# INT_mPCIeX2_SIM.net
KiCad netlist of a schematic drawn in Altium Designer
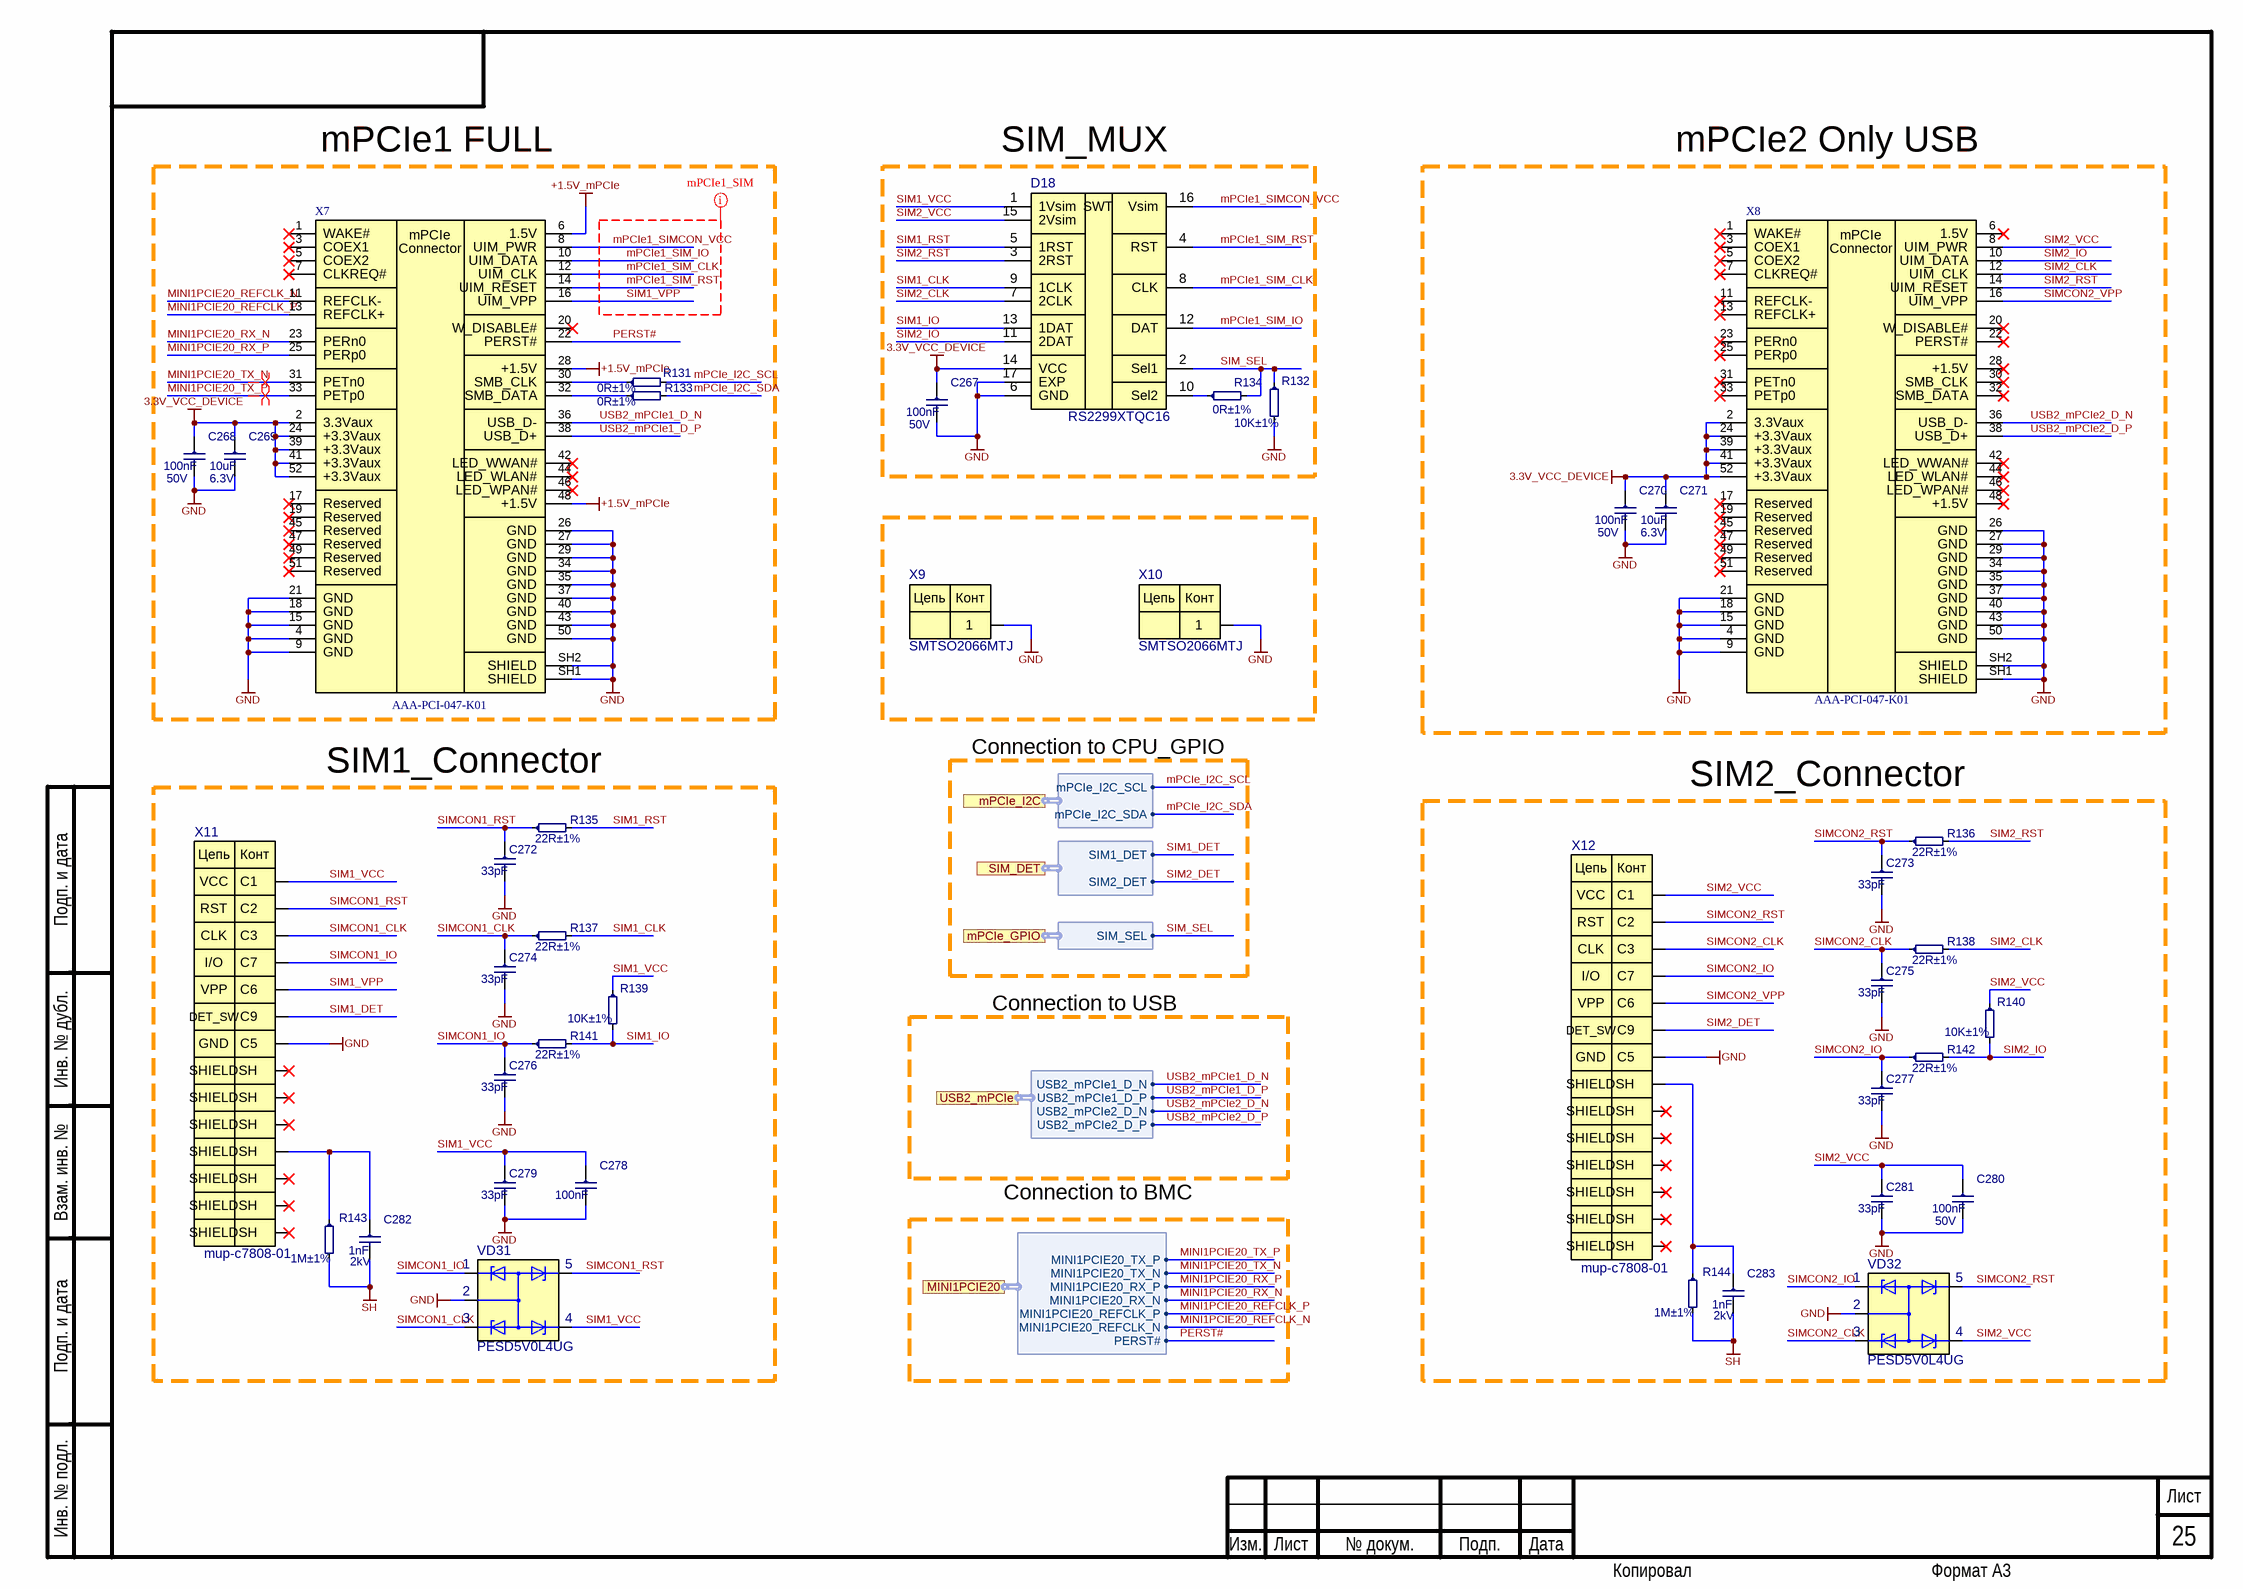
[diagram p0: INT_mPCIeX2_SIM.SchDoc]

(export (version "E")
  (design (tool "Eeschema 10.0.6"))
  (components
    (comp (ref "C267")
      (value "100nF")
      (footprint "C0402")
      (description "Ceramic Capacitor 0402 100nF ±10% 50V X7R")
      (fields
        (field (name "VOLTAGE") "50V")
        (field (name "PART NUMBER") "0402-X7R-50V-0.1uF±10%")
        (field (name "TOLERANCE") "10%")
      )
      (libsource (lib "ATB") (part "C"))
    )
    (comp (ref "C268")
      (value "100nF")
      (footprint "C0402")
      (description "Ceramic Capacitor 0402 100nF ±10% 50V X7R")
      (fields
        (field (name "VOLTAGE") "50V")
        (field (name "PART NUMBER") "0402-X7R-50V-0.1uF±10%")
        (field (name "TOLERANCE") "10%")
      )
      (libsource (lib "ATB") (part "C"))
    )
    (comp (ref "C269")
      (value "10uF")
      (footprint "C0402")
      (fields
        (field (name "VOLTAGE") "6.3V")
        (field (name "PART NUMBER") "0402-X5R-6.3V-10uF±20%")
        (field (name "TOLERANCE") "20%")
        (field (name "MANUFACTURER") "Yageo")
      )
      (libsource (lib "ATB") (part "C"))
    )
    (comp (ref "C270")
      (value "100nF")
      (footprint "C0402")
      (description "Ceramic Capacitor 0402 100nF ±10% 50V X7R")
      (fields
        (field (name "VOLTAGE") "50V")
        (field (name "PART NUMBER") "0402-X7R-50V-0.1uF±10%")
        (field (name "TOLERANCE") "10%")
      )
      (libsource (lib "ATB") (part "C"))
    )
    (comp (ref "C271")
      (value "10uF")
      (footprint "C0402")
      (fields
        (field (name "VOLTAGE") "6.3V")
        (field (name "PART NUMBER") "0402-X5R-6.3V-10uF±20%")
        (field (name "TOLERANCE") "20%")
        (field (name "MANUFACTURER") "Yageo")
      )
      (libsource (lib "ATB") (part "C"))
    )
    (comp (ref "C272")
      (value "33pF")
      (footprint "C0402")
      (fields
        (field (name "VOLTAGE") "50V")
        (field (name "PART NUMBER") "0402-NP0-50V-33pF±5%")
        (field (name "TOLERANCE") "5%")
      )
      (libsource (lib "ATB") (part "C"))
    )
    (comp (ref "C273")
      (value "33pF")
      (footprint "C0402")
      (fields
        (field (name "VOLTAGE") "50V")
        (field (name "PART NUMBER") "0402-NP0-50V-33pF±5%")
        (field (name "TOLERANCE") "5%")
      )
      (libsource (lib "ATB") (part "C"))
    )
    (comp (ref "C274")
      (value "33pF")
      (footprint "C0402")
      (fields
        (field (name "VOLTAGE") "50V")
        (field (name "PART NUMBER") "0402-NP0-50V-33pF±5%")
        (field (name "TOLERANCE") "5%")
      )
      (libsource (lib "ATB") (part "C"))
    )
    (comp (ref "C275")
      (value "33pF")
      (footprint "C0402")
      (fields
        (field (name "VOLTAGE") "50V")
        (field (name "PART NUMBER") "0402-NP0-50V-33pF±5%")
        (field (name "TOLERANCE") "5%")
      )
      (libsource (lib "ATB") (part "C"))
    )
    (comp (ref "C276")
      (value "33pF")
      (footprint "C0402")
      (fields
        (field (name "VOLTAGE") "50V")
        (field (name "PART NUMBER") "0402-NP0-50V-33pF±5%")
        (field (name "TOLERANCE") "5%")
      )
      (libsource (lib "ATB") (part "C"))
    )
    (comp (ref "C277")
      (value "33pF")
      (footprint "C0402")
      (fields
        (field (name "VOLTAGE") "50V")
        (field (name "PART NUMBER") "0402-NP0-50V-33pF±5%")
        (field (name "TOLERANCE") "5%")
      )
      (libsource (lib "ATB") (part "C"))
    )
    (comp (ref "C278")
      (value "100nF")
      (footprint "C0402")
      (description "Ceramic Capacitor 0402 100nF ±10% 50V X7R")
      (fields (field (name "VOLTAGE") "50V") (field (name "PART NUMBER") "0402-X7R-50V-0.1uF±10%"))
      (libsource (lib "ATB") (part "C"))
    )
    (comp (ref "C279")
      (value "33pF")
      (footprint "C0402")
      (fields
        (field (name "VOLTAGE") "50V")
        (field (name "PART NUMBER") "0402-NP0-50V-33pF±5%")
        (field (name "TOLERANCE") "5%")
      )
      (libsource (lib "ATB") (part "C"))
    )
    (comp (ref "C280")
      (value "100nF")
      (footprint "C0402")
      (description "Ceramic Capacitor 0402 100nF ±10% 50V X7R")
      (fields
        (field (name "VOLTAGE") "50V")
        (field (name "PART NUMBER") "0402-X7R-50V-0.1uF±10%")
        (field (name "TOLERANCE") "10%")
      )
      (libsource (lib "ATB") (part "C"))
    )
    (comp (ref "C281")
      (value "33pF")
      (footprint "C0402")
      (fields
        (field (name "VOLTAGE") "50V")
        (field (name "PART NUMBER") "0402-NP0-50V-33pF±5%")
        (field (name "TOLERANCE") "5%")
      )
      (libsource (lib "ATB") (part "C"))
    )
    (comp (ref "C282")
      (value "1nF")
      (footprint "C1812")
      (fields
        (field (name "VOLTAGE") "2kV")
        (field (name "PART NUMBER") "1812-C0G-2kV-1nF±10%")
        (field (name "TOLERANCE") "5%")
        (field (name "MANUFACTURER") "FH")
      )
      (libsource (lib "ATB") (part "C"))
    )
    (comp (ref "C283")
      (value "1nF")
      (footprint "C1812")
      (fields
        (field (name "VOLTAGE") "2kV")
        (field (name "PART NUMBER") "1812-C0G-2kV-1nF±10%")
        (field (name "TOLERANCE") "5%")
        (field (name "MANUFACTURER") "FH")
      )
      (libsource (lib "ATB") (part "C"))
    )
    (comp (ref "D18")
      (value "RS2299XTQC16")
      (footprint "RS2299XTQC16")
      (description "Analog Switches")
      (fields (field (name "MANUFACTURER") "RUNIC Tech"))
      (libsource (lib "LIB_RK") (part "RS2299XTQC16"))
    )
    (comp (ref "R131")
      (value "0R±1%")
      (footprint "R0402")
      (description "Chip Resistor 0402 0Ω ±1% 50V ±100ppm/℃ Thick Film")
      (fields (field (name "PART NUMBER") "0402-0.0625W-0R-100ppm±1%") (field (name "TOLERANCE") "1%"))
      (libsource (lib "ATB") (part "R"))
    )
    (comp (ref "R132")
      (value "10K±1%")
      (footprint "R0402")
      (description "Chip Resistor 0402 10kΩ ±1% 50V ±100ppm/℃ Thick Film")
      (fields (field (name "PART NUMBER") "0402-0.0625W-10K-100ppm±1%") (field (name "TOLERANCE") "1%"))
      (libsource (lib "ATB") (part "R"))
    )
    (comp (ref "R133")
      (value "0R±1%")
      (footprint "R0402")
      (description "Chip Resistor 0402 0Ω ±1% 50V ±100ppm/℃ Thick Film")
      (fields (field (name "PART NUMBER") "0402-0.0625W-0R-100ppm±1%") (field (name "TOLERANCE") "1%"))
      (libsource (lib "ATB") (part "R"))
    )
    (comp (ref "R134")
      (value "0R±1%")
      (footprint "R0402")
      (description "Chip Resistor 0402 0Ω ±1% 50V ±100ppm/℃ Thick Film")
      (fields (field (name "PART NUMBER") "0402-0.0625W-0R-100ppm±1%") (field (name "TOLERANCE") "1%"))
      (libsource (lib "ATB") (part "R"))
    )
    (comp (ref "R135")
      (value "22R±1%")
      (footprint "R0402")
      (description "Chip Resistor 0402 22Ω ±1% 50V ±100ppm/℃ Thick Film")
      (fields (field (name "PART NUMBER") "0402-0.0625W-22R-100ppm±1%") (field (name "TOLERANCE") "1%"))
      (libsource (lib "ATB") (part "R"))
    )
    (comp (ref "R136")
      (value "22R±1%")
      (footprint "R0402")
      (description "Chip Resistor 0402 22Ω ±1% 50V ±100ppm/℃ Thick Film")
      (fields (field (name "PART NUMBER") "0402-0.0625W-22R-100ppm±1%") (field (name "TOLERANCE") "1%"))
      (libsource (lib "ATB") (part "R"))
    )
    (comp (ref "R137")
      (value "22R±1%")
      (footprint "R0402")
      (description "Chip Resistor 0402 22Ω ±1% 50V ±100ppm/℃ Thick Film")
      (fields (field (name "PART NUMBER") "0402-0.0625W-22R-100ppm±1%") (field (name "TOLERANCE") "1%"))
      (libsource (lib "ATB") (part "R"))
    )
    (comp (ref "R138")
      (value "22R±1%")
      (footprint "R0402")
      (description "Chip Resistor 0402 22Ω ±1% 50V ±100ppm/℃ Thick Film")
      (fields (field (name "PART NUMBER") "0402-0.0625W-22R-100ppm±1%") (field (name "TOLERANCE") "1%"))
      (libsource (lib "ATB") (part "R"))
    )
    (comp (ref "R139")
      (value "10K±1%")
      (footprint "R0402")
      (description "Chip Resistor 0402 10kΩ ±1% 50V ±100ppm/℃ Thick Film")
      (fields (field (name "PART NUMBER") "0402-0.0625W-10K-100ppm±1%") (field (name "TOLERANCE") "1%"))
      (libsource (lib "ATB") (part "R"))
    )
    (comp (ref "R140")
      (value "10K±1%")
      (footprint "R0402")
      (description "Chip Resistor 0402 10kΩ ±1% 50V ±100ppm/℃ Thick Film")
      (fields (field (name "PART NUMBER") "0402-0.0625W-10K-100ppm±1%") (field (name "TOLERANCE") "1%"))
      (libsource (lib "ATB") (part "R"))
    )
    (comp (ref "R141")
      (value "22R±1%")
      (footprint "R0402")
      (description "Chip Resistor 0402 22Ω ±1% 50V ±100ppm/℃ Thick Film")
      (fields (field (name "PART NUMBER") "0402-0.0625W-22R-100ppm±1%") (field (name "TOLERANCE") "1%"))
      (libsource (lib "ATB") (part "R"))
    )
    (comp (ref "R142")
      (value "22R±1%")
      (footprint "R0402")
      (description "Chip Resistor 0402 22Ω ±1% 50V ±100ppm/℃ Thick Film")
      (fields (field (name "PART NUMBER") "0402-0.0625W-22R-100ppm±1%") (field (name "TOLERANCE") "1%"))
      (libsource (lib "ATB") (part "R"))
    )
    (comp (ref "R143")
      (value "1M±1%")
      (footprint "R1206")
      (description "Chip Resistor 1206 1MΩ ±1% 200V ±100ppm/℃ Thick Film")
      (fields (field (name "PART NUMBER") "1206-0.25W-1M-100ppm±1%") (field (name "TOLERANCE") "1%"))
      (libsource (lib "ATB") (part "R"))
    )
    (comp (ref "R144")
      (value "1M±1%")
      (footprint "R1206")
      (description "Chip Resistor 1206 1MΩ ±1% 200V ±100ppm/℃ Thick Film")
      (fields (field (name "PART NUMBER") "1206-0.25W-1M-100ppm±1%") (field (name "TOLERANCE") "1%"))
      (libsource (lib "ATB") (part "R"))
    )
    (comp (ref "VD31")
      (value "PESD5V0L4UG")
      (footprint "TSSOP5-5")
      (description "Low capacitance unidirectional quadruple ESD protectiondiode arrays")
      (fields (field (name "MANUFACTURER") "Tech Public Co."))
      (libsource (lib "ATB") (part "PESDxL4UG/W"))
    )
    (comp (ref "VD32")
      (value "PESD5V0L4UG")
      (footprint "TSSOP5-5")
      (description "Low capacitance unidirectional quadruple ESD protectiondiode arrays")
      (fields (field (name "MANUFACTURER") "Tech Public Co."))
      (libsource (lib "ATB") (part "PESDxL4UG/W"))
    )
    (comp (ref "X7")
      (value "AAA-PCI-047-K01")
      (footprint "AAA-PCI-047-K01")
      (description "mPCI-E Surface Mount 52 SMD,P=0.8mm Card Edge Connectors")
      (fields (field (name "MANUFACTURER") "LOTES"))
      (libsource (lib "LIB_RK") (part "AAA-PCI-047-K01"))
    )
    (comp (ref "X8")
      (value "AAA-PCI-047-K01")
      (footprint "AAA-PCI-047-K01")
      (description "mPCI-E Surface Mount 52 SMD,P=0.8mm Card Edge Connectors")
      (fields (field (name "MANUFACTURER") "LOTES"))
      (libsource (lib "LIB_RK") (part "AAA-PCI-047-K01"))
    )
    (comp (ref "X9")
      (value "SMTSO2066MTJ")
      (footprint "SMTSO2066MTJ")
      (fields (field (name "MANUFACTURER") "Sinhoo"))
      (libsource (lib "LIB_RK") (part "SMTSO2066MTJ"))
    )
    (comp (ref "X10")
      (value "SMTSO2066MTJ")
      (footprint "SMTSO2066MTJ")
      (fields (field (name "MANUFACTURER") "Sinhoo"))
      (libsource (lib "LIB_RK") (part "SMTSO2066MTJ"))
    )
    (comp (ref "X11")
      (value "mup-c7808-01")
      (footprint "mup-c7808")
      (fields (field (name "MANUFACTURER") "MUP"))
      (libsource (lib "LIB_RK") (part "mup-c7808"))
    )
    (comp (ref "X12")
      (value "mup-c7808-01")
      (footprint "mup-c7808")
      (fields (field (name "MANUFACTURER") "MUP"))
      (libsource (lib "LIB_RK") (part "mup-c7808"))
    )
  )
  (nets
    (net (code "6") (name "+1.5V_mPCIe") (class "Default")
      (node (ref "X7") (pin "28") (pinfunction "+1.5V_28") (pintype "passive"))
      (node (ref "X7") (pin "48") (pinfunction "+1.5V_48") (pintype "passive"))
      (node (ref "X7") (pin "6") (pinfunction "1.5V_6") (pintype "passive"))
    )
    (net (code "7") (name "/MINI1PCIE20_REFCLK_N") (class "Default")
      (node (ref "X7") (pin "11") (pinfunction "REFCLK-_11") (pintype "passive"))
    )
    (net (code "8") (name "/MINI1PCIE20_REFCLK_P") (class "Default")
      (node (ref "X7") (pin "13") (pinfunction "REFCLK+_13") (pintype "passive"))
    )
    (net (code "9") (name "/MINI1PCIE20_RX_N") (class "Default")
      (node (ref "X7") (pin "23") (pinfunction "PERn0_23") (pintype "passive"))
    )
    (net (code "10") (name "/MINI1PCIE20_RX_P") (class "Default")
      (node (ref "X7") (pin "25") (pinfunction "PERp0_25") (pintype "passive"))
    )
    (net (code "11") (name "/MINI1PCIE20_TX_N") (class "Default")
      (node (ref "X7") (pin "31") (pinfunction "PETn0_31") (pintype "passive"))
    )
    (net (code "12") (name "/MINI1PCIE20_TX_P") (class "Default")
      (node (ref "X7") (pin "33") (pinfunction "РЕТр0_33") (pintype "passive"))
    )
    (net (code "13") (name "/PERST#") (class "Default")
      (node (ref "X7") (pin "22") (pinfunction "PERST#_22") (pintype "passive"))
    )
    (net (code "14") (name "/SIM1_CLK") (class "Default")
      (node (ref "D18") (pin "9") (pinfunction "1CLK_9") (pintype "passive"))
      (node (ref "R137") (pin "2") (pinfunction "2_2") (pintype "passive"))
    )
    (net (code "15") (name "/SIM1_DET") (class "Default")
      (node (ref "X11") (pin "C9") (pinfunction "C9_C9") (pintype "passive"))
    )
    (net (code "16") (name "/SIM1_IO") (class "Default")
      (node (ref "D18") (pin "13") (pinfunction "1DAT_13") (pintype "passive"))
      (node (ref "R139") (pin "2") (pinfunction "2_2") (pintype "passive"))
      (node (ref "R141") (pin "2") (pinfunction "2_2") (pintype "passive"))
    )
    (net (code "17") (name "/SIM1_RST") (class "Default")
      (node (ref "D18") (pin "5") (pinfunction "1RST_5") (pintype "passive"))
      (node (ref "R135") (pin "2") (pinfunction "2_2") (pintype "passive"))
    )
    (net (code "18") (name "/SIM1_VCC") (class "Default")
      (node (ref "C278") (pin "1") (pinfunction "1_1") (pintype "passive"))
      (node (ref "C279") (pin "1") (pinfunction "1_1") (pintype "passive"))
      (node (ref "D18") (pin "1") (pinfunction "1Vsim_1") (pintype "passive"))
      (node (ref "R139") (pin "1") (pinfunction "1_1") (pintype "passive"))
      (node (ref "VD31") (pin "4") (pinfunction "4_4") (pintype "passive"))
      (node (ref "X11") (pin "C1") (pinfunction "C1_C1") (pintype "passive"))
    )
    (net (code "19") (name "/SIM1_VPP") (class "Default")
      (node (ref "X11") (pin "C6") (pinfunction "C6_C6") (pintype "passive"))
      (node (ref "X7") (pin "16") (pinfunction "UIM_VPP_16") (pintype "passive"))
    )
    (net (code "20") (name "/SIM2_CLK") (class "Default")
      (node (ref "D18") (pin "7") (pinfunction "2CLK_7") (pintype "passive"))
      (node (ref "R138") (pin "2") (pinfunction "2_2") (pintype "passive"))
      (node (ref "X8") (pin "12") (pinfunction "UIM_CLK_12") (pintype "passive"))
    )
    (net (code "21") (name "/SIM2_DET") (class "Default")
      (node (ref "X12") (pin "C9") (pinfunction "C9_C9") (pintype "passive"))
    )
    (net (code "22") (name "/SIM2_IO") (class "Default")
      (node (ref "D18") (pin "11") (pinfunction "2DAT_11") (pintype "passive"))
      (node (ref "R140") (pin "2") (pinfunction "2_2") (pintype "passive"))
      (node (ref "R142") (pin "2") (pinfunction "2_2") (pintype "passive"))
      (node (ref "X8") (pin "10") (pinfunction "UIM_DATA_10") (pintype "passive"))
    )
    (net (code "23") (name "/SIM2_RST") (class "Default")
      (node (ref "D18") (pin "3") (pinfunction "2RST_3") (pintype "passive"))
      (node (ref "R136") (pin "2") (pinfunction "2_2") (pintype "passive"))
      (node (ref "X8") (pin "14") (pinfunction "UIM_RESET_14") (pintype "passive"))
    )
    (net (code "24") (name "/SIM2_VCC") (class "Default")
      (node (ref "C280") (pin "1") (pinfunction "1_1") (pintype "passive"))
      (node (ref "C281") (pin "1") (pinfunction "1_1") (pintype "passive"))
      (node (ref "D18") (pin "15") (pinfunction "2Vsim_15") (pintype "passive"))
      (node (ref "R140") (pin "1") (pinfunction "1_1") (pintype "passive"))
      (node (ref "VD32") (pin "4") (pinfunction "4_4") (pintype "passive"))
      (node (ref "X12") (pin "C1") (pinfunction "C1_C1") (pintype "passive"))
      (node (ref "X8") (pin "8") (pinfunction "UIM_PWR_8") (pintype "passive"))
    )
    (net (code "25") (name "/SIMCON1_CLK") (class "Default")
      (node (ref "C274") (pin "1") (pinfunction "1_1") (pintype "passive"))
      (node (ref "R137") (pin "1") (pinfunction "1_1") (pintype "passive"))
      (node (ref "VD31") (pin "3") (pinfunction "3_3") (pintype "passive"))
      (node (ref "X11") (pin "C3") (pinfunction "C3_C3") (pintype "passive"))
    )
    (net (code "26") (name "/SIMCON1_IO") (class "Default")
      (node (ref "C276") (pin "1") (pinfunction "1_1") (pintype "passive"))
      (node (ref "R141") (pin "1") (pinfunction "1_1") (pintype "passive"))
      (node (ref "VD31") (pin "1") (pinfunction "1_1") (pintype "passive"))
      (node (ref "X11") (pin "C7") (pinfunction "C7_C7") (pintype "passive"))
    )
    (net (code "27") (name "/SIMCON1_RST") (class "Default")
      (node (ref "C272") (pin "1") (pinfunction "1_1") (pintype "passive"))
      (node (ref "R135") (pin "1") (pinfunction "1_1") (pintype "passive"))
      (node (ref "VD31") (pin "5") (pinfunction "5_5") (pintype "passive"))
      (node (ref "X11") (pin "C2") (pinfunction "C2_C2") (pintype "passive"))
    )
    (net (code "28") (name "/SIMCON2_CLK") (class "Default")
      (node (ref "C275") (pin "1") (pinfunction "1_1") (pintype "passive"))
      (node (ref "R138") (pin "1") (pinfunction "1_1") (pintype "passive"))
      (node (ref "VD32") (pin "3") (pinfunction "3_3") (pintype "passive"))
      (node (ref "X12") (pin "C3") (pinfunction "C3_C3") (pintype "passive"))
    )
    (net (code "29") (name "/SIMCON2_IO") (class "Default")
      (node (ref "C277") (pin "1") (pinfunction "1_1") (pintype "passive"))
      (node (ref "R142") (pin "1") (pinfunction "1_1") (pintype "passive"))
      (node (ref "VD32") (pin "1") (pinfunction "1_1") (pintype "passive"))
      (node (ref "X12") (pin "C7") (pinfunction "C7_C7") (pintype "passive"))
    )
    (net (code "30") (name "/SIMCON2_RST") (class "Default")
      (node (ref "C273") (pin "1") (pinfunction "1_1") (pintype "passive"))
      (node (ref "R136") (pin "1") (pinfunction "1_1") (pintype "passive"))
      (node (ref "VD32") (pin "5") (pinfunction "5_5") (pintype "passive"))
      (node (ref "X12") (pin "C2") (pinfunction "C2_C2") (pintype "passive"))
    )
    (net (code "31") (name "/SIMCON2_VPP") (class "Default")
      (node (ref "X12") (pin "C6") (pinfunction "C6_C6") (pintype "passive"))
      (node (ref "X8") (pin "16") (pinfunction "UIM_VPP_16") (pintype "passive"))
    )
    (net (code "32") (name "/SIM_SEL") (class "Default")
      (node (ref "D18") (pin "2") (pinfunction "Sel1_2") (pintype "passive"))
      (node (ref "R132") (pin "1") (pinfunction "1_1") (pintype "passive"))
      (node (ref "R134") (pin "2") (pinfunction "2_2") (pintype "passive"))
    )
    (net (code "33") (name "/USB2_mPCIe1_D_N") (class "Default")
      (node (ref "X7") (pin "36") (pinfunction "USB_D-_36") (pintype "passive"))
    )
    (net (code "34") (name "/USB2_mPCIe1_D_P") (class "Default")
      (node (ref "X7") (pin "38") (pinfunction "USB_D+_38") (pintype "passive"))
    )
    (net (code "35") (name "/USB2_mPCIe2_D_N") (class "Default")
      (node (ref "X8") (pin "36") (pinfunction "USB_D-_36") (pintype "passive"))
    )
    (net (code "36") (name "/USB2_mPCIe2_D_P") (class "Default")
      (node (ref "X8") (pin "38") (pinfunction "USB_D+_38") (pintype "passive"))
    )
    (net (code "37") (name "/mPCIe1_SIMCON_VCC") (class "Default")
      (node (ref "D18") (pin "16") (pinfunction "Vsim_16") (pintype "passive"))
      (node (ref "X7") (pin "8") (pinfunction "UIM_PWR_8") (pintype "passive"))
    )
    (net (code "38") (name "/mPCIe1_SIM_CLK") (class "Default")
      (node (ref "D18") (pin "8") (pinfunction "CLK_8") (pintype "passive"))
      (node (ref "X7") (pin "12") (pinfunction "UIM_CLK_12") (pintype "passive"))
    )
    (net (code "39") (name "/mPCIe1_SIM_IO") (class "Default")
      (node (ref "D18") (pin "12") (pinfunction "DAT_12") (pintype "passive"))
      (node (ref "X7") (pin "10") (pinfunction "UIM_DATA_10") (pintype "passive"))
    )
    (net (code "40") (name "/mPCIe1_SIM_RST") (class "Default")
      (node (ref "D18") (pin "4") (pinfunction "RST_4") (pintype "passive"))
      (node (ref "X7") (pin "14") (pinfunction "UIM_RESET_14") (pintype "passive"))
    )
    (net (code "41") (name "/mPCIe_I2C_SCL") (class "Default")
      (node (ref "R131") (pin "2") (pinfunction "2_2") (pintype "passive"))
    )
    (net (code "42") (name "/mPCIe_I2C_SDA") (class "Default")
      (node (ref "R133") (pin "2") (pinfunction "2_2") (pintype "passive"))
    )
    (net (code "48") (name "3.3V_VCC_DEVICE") (class "Default")
      (node (ref "C267") (pin "1") (pinfunction "1_1") (pintype "passive"))
      (node (ref "C268") (pin "1") (pinfunction "1_1") (pintype "passive"))
      (node (ref "C269") (pin "1") (pinfunction "1_1") (pintype "passive"))
      (node (ref "C270") (pin "1") (pinfunction "1_1") (pintype "passive"))
      (node (ref "C271") (pin "1") (pinfunction "1_1") (pintype "passive"))
      (node (ref "D18") (pin "14") (pinfunction "VCC_14") (pintype "passive"))
      (node (ref "X7") (pin "2") (pinfunction "3.3Vaux_2") (pintype "passive"))
      (node (ref "X7") (pin "24") (pinfunction "+3.3Vaux_24") (pintype "passive"))
      (node (ref "X7") (pin "39") (pinfunction "+3.3Vaux_39") (pintype "passive"))
      (node (ref "X7") (pin "41") (pinfunction "+3.3Vaux_41") (pintype "passive"))
      (node (ref "X7") (pin "52") (pinfunction "+3.3Vaux_52") (pintype "passive"))
      (node (ref "X8") (pin "2") (pinfunction "3.3Vaux_2") (pintype "passive"))
      (node (ref "X8") (pin "24") (pinfunction "+3.3Vaux_24") (pintype "passive"))
      (node (ref "X8") (pin "39") (pinfunction "+3.3Vaux_39") (pintype "passive"))
      (node (ref "X8") (pin "41") (pinfunction "+3.3Vaux_41") (pintype "passive"))
      (node (ref "X8") (pin "52") (pinfunction "+3.3Vaux_52") (pintype "passive"))
    )
    (net (code "49") (name "GND") (class "Default")
      (node (ref "C267") (pin "2") (pinfunction "2_2") (pintype "passive"))
      (node (ref "C268") (pin "2") (pinfunction "2_2") (pintype "passive"))
      (node (ref "C269") (pin "2") (pinfunction "2_2") (pintype "passive"))
      (node (ref "C270") (pin "2") (pinfunction "2_2") (pintype "passive"))
      (node (ref "C271") (pin "2") (pinfunction "2_2") (pintype "passive"))
      (node (ref "C272") (pin "2") (pinfunction "2_2") (pintype "passive"))
      (node (ref "C273") (pin "2") (pinfunction "2_2") (pintype "passive"))
      (node (ref "C274") (pin "2") (pinfunction "2_2") (pintype "passive"))
      (node (ref "C275") (pin "2") (pinfunction "2_2") (pintype "passive"))
      (node (ref "C276") (pin "2") (pinfunction "2_2") (pintype "passive"))
      (node (ref "C277") (pin "2") (pinfunction "2_2") (pintype "passive"))
      (node (ref "C278") (pin "2") (pinfunction "2_2") (pintype "passive"))
      (node (ref "C279") (pin "2") (pinfunction "2_2") (pintype "passive"))
      (node (ref "C280") (pin "2") (pinfunction "2_2") (pintype "passive"))
      (node (ref "C281") (pin "2") (pinfunction "2_2") (pintype "passive"))
      (node (ref "D18") (pin "17") (pinfunction "EXP_17") (pintype "passive"))
      (node (ref "D18") (pin "6") (pinfunction "GND_6") (pintype "passive"))
      (node (ref "R132") (pin "2") (pinfunction "2_2") (pintype "passive"))
      (node (ref "VD31") (pin "2") (pinfunction "2_2") (pintype "passive"))
      (node (ref "VD32") (pin "2") (pinfunction "2_2") (pintype "passive"))
      (node (ref "X10") (pin "1") (pinfunction "1_1") (pintype "passive"))
      (node (ref "X11") (pin "C5") (pinfunction "C5_C5") (pintype "passive"))
      (node (ref "X12") (pin "C5") (pinfunction "C5_C5") (pintype "passive"))
      (node (ref "X7") (pin "15") (pinfunction "GND_15") (pintype "passive"))
      (node (ref "X7") (pin "18") (pinfunction "GND_18") (pintype "passive"))
      (node (ref "X7") (pin "21") (pinfunction "GND_21") (pintype "passive"))
      (node (ref "X7") (pin "26") (pinfunction "GND_26") (pintype "passive"))
      (node (ref "X7") (pin "27") (pinfunction "GND_27") (pintype "passive"))
      (node (ref "X7") (pin "29") (pinfunction "GND_29") (pintype "passive"))
      (node (ref "X7") (pin "34") (pinfunction "GND_34") (pintype "passive"))
      (node (ref "X7") (pin "35") (pinfunction "GND_35") (pintype "passive"))
      (node (ref "X7") (pin "37") (pinfunction "GND_37") (pintype "passive"))
      (node (ref "X7") (pin "4") (pinfunction "GND_4") (pintype "passive"))
      (node (ref "X7") (pin "40") (pinfunction "GND_40") (pintype "passive"))
      (node (ref "X7") (pin "43") (pinfunction "GND_43") (pintype "passive"))
      (node (ref "X7") (pin "50") (pinfunction "GND_50") (pintype "passive"))
      (node (ref "X7") (pin "9") (pinfunction "GND_9") (pintype "passive"))
      (node (ref "X7") (pin "SH1") (pinfunction "SHIELD_SH1") (pintype "passive"))
      (node (ref "X7") (pin "SH2") (pinfunction "SHIELD_SH2") (pintype "passive"))
      (node (ref "X8") (pin "15") (pinfunction "GND_15") (pintype "passive"))
      (node (ref "X8") (pin "18") (pinfunction "GND_18") (pintype "passive"))
      (node (ref "X8") (pin "21") (pinfunction "GND_21") (pintype "passive"))
      (node (ref "X8") (pin "26") (pinfunction "GND_26") (pintype "passive"))
      (node (ref "X8") (pin "27") (pinfunction "GND_27") (pintype "passive"))
      (node (ref "X8") (pin "29") (pinfunction "GND_29") (pintype "passive"))
      (node (ref "X8") (pin "34") (pinfunction "GND_34") (pintype "passive"))
      (node (ref "X8") (pin "35") (pinfunction "GND_35") (pintype "passive"))
      (node (ref "X8") (pin "37") (pinfunction "GND_37") (pintype "passive"))
      (node (ref "X8") (pin "4") (pinfunction "GND_4") (pintype "passive"))
      (node (ref "X8") (pin "40") (pinfunction "GND_40") (pintype "passive"))
      (node (ref "X8") (pin "43") (pinfunction "GND_43") (pintype "passive"))
      (node (ref "X8") (pin "50") (pinfunction "GND_50") (pintype "passive"))
      (node (ref "X8") (pin "9") (pinfunction "GND_9") (pintype "passive"))
      (node (ref "X8") (pin "SH1") (pinfunction "SHIELD_SH1") (pintype "passive"))
      (node (ref "X8") (pin "SH2") (pinfunction "SHIELD_SH2") (pintype "passive"))
      (node (ref "X9") (pin "1") (pinfunction "1_1") (pintype "passive"))
    )
    (net (code "50") (name "Net-(C282-Pad1)") (class "Default")
      (node (ref "C282") (pin "1") (pinfunction "1_1") (pintype "passive"))
      (node (ref "R143") (pin "1") (pinfunction "1_1") (pintype "passive"))
      (node (ref "X11") (pin "SH4") (pinfunction "SH_SH4") (pintype "passive"))
    )
    (net (code "51") (name "Net-(C283-Pad1)") (class "Default")
      (node (ref "C283") (pin "1") (pinfunction "1_1") (pintype "passive"))
      (node (ref "R144") (pin "1") (pinfunction "1_1") (pintype "passive"))
      (node (ref "X12") (pin "SH1") (pinfunction "SH_SH1") (pintype "passive"))
    )
    (net (code "52") (name "Net-(D18-Sel2)") (class "Default")
      (node (ref "D18") (pin "10") (pinfunction "Sel2_10") (pintype "passive"))
      (node (ref "R134") (pin "1") (pinfunction "1_1") (pintype "passive"))
    )
    (net (code "53") (name "Net-(X7-SMB_CLK)") (class "Default")
      (node (ref "R131") (pin "1") (pinfunction "1_1") (pintype "passive"))
      (node (ref "X7") (pin "30") (pinfunction "SMB_CLK_30") (pintype "passive"))
    )
    (net (code "54") (name "Net-(X7-SMB_DATA)") (class "Default")
      (node (ref "R133") (pin "1") (pinfunction "1_1") (pintype "passive"))
      (node (ref "X7") (pin "32") (pinfunction "SMB_DATA_32") (pintype "passive"))
    )
    (net (code "55") (name "SH") (class "Default")
      (node (ref "C282") (pin "2") (pinfunction "2_2") (pintype "passive"))
      (node (ref "C283") (pin "2") (pinfunction "2_2") (pintype "passive"))
      (node (ref "R143") (pin "2") (pinfunction "2_2") (pintype "passive"))
      (node (ref "R144") (pin "2") (pinfunction "2_2") (pintype "passive"))
    )
    (net (code "56") (name "unconnected-(X7-CLKREQ#-Pad7)") (class "Default")
      (node (ref "X7") (pin "7") (pinfunction "CLKREQ#_7") (pintype "passive+no_connect"))
    )
    (net (code "57") (name "unconnected-(X7-LED_WLAN#-Pad44)") (class "Default")
      (node (ref "X7") (pin "44") (pinfunction "LED_WLAN#_44") (pintype "passive+no_connect"))
    )
    (net (code "58") (name "unconnected-(X7-LED_WPAN#-Pad46)") (class "Default")
      (node (ref "X7") (pin "46") (pinfunction "LED_WPAN#_46") (pintype "passive+no_connect"))
    )
    (net (code "59") (name "unconnected-(X7-LED_WWAN#-Pad42)") (class "Default")
      (node (ref "X7") (pin "42") (pinfunction "LED_WWAN#_42") (pintype "passive+no_connect"))
    )
    (net (code "60") (name "unconnected-(X7-Reserved-Pad17)") (class "Default")
      (node (ref "X7") (pin "17") (pinfunction "Reserved_17") (pintype "passive+no_connect"))
    )
    (net (code "61") (name "unconnected-(X7-Reserved-Pad19)") (class "Default")
      (node (ref "X7") (pin "19") (pinfunction "Reserved_19") (pintype "passive+no_connect"))
    )
    (net (code "62") (name "unconnected-(X7-Reserved-Pad45)") (class "Default")
      (node (ref "X7") (pin "45") (pinfunction "Reserved_45") (pintype "passive+no_connect"))
    )
    (net (code "63") (name "unconnected-(X7-Reserved-Pad47)") (class "Default")
      (node (ref "X7") (pin "47") (pinfunction "Reserved_47") (pintype "passive+no_connect"))
    )
    (net (code "64") (name "unconnected-(X7-Reserved-Pad49)") (class "Default")
      (node (ref "X7") (pin "49") (pinfunction "Reserved_49") (pintype "passive+no_connect"))
    )
    (net (code "65") (name "unconnected-(X7-Reserved-Pad51)") (class "Default")
      (node (ref "X7") (pin "51") (pinfunction "Reserved_51") (pintype "passive+no_connect"))
    )
    (net (code "66") (name "unconnected-(X7-WAKE#-Pad1)") (class "Default")
      (node (ref "X7") (pin "1") (pinfunction "WAKE#_1") (pintype "passive+no_connect"))
    )
    (net (code "67") (name "unconnected-(X7-W_DISABLE#-Pad20)") (class "Default")
      (node (ref "X7") (pin "20") (pinfunction "W_DISABLE#_20") (pintype "passive+no_connect"))
    )
    (net (code "68") (name "unconnected-(X7-СОЕХ1-Pad3)") (class "Default")
      (node (ref "X7") (pin "3") (pinfunction "СОЕХ1_3") (pintype "passive+no_connect"))
    )
    (net (code "69") (name "unconnected-(X7-СОЕХ2-Pad5)") (class "Default")
      (node (ref "X7") (pin "5") (pinfunction "СОЕХ2_5") (pintype "passive+no_connect"))
    )
    (net (code "70") (name "unconnected-(X8-+1.5V-Pad28)") (class "Default")
      (node (ref "X8") (pin "28") (pinfunction "+1.5V_28") (pintype "passive+no_connect"))
    )
    (net (code "71") (name "unconnected-(X8-+1.5V-Pad48)") (class "Default")
      (node (ref "X8") (pin "48") (pinfunction "+1.5V_48") (pintype "passive+no_connect"))
    )
    (net (code "72") (name "unconnected-(X8-1.5V-Pad6)") (class "Default")
      (node (ref "X8") (pin "6") (pinfunction "1.5V_6") (pintype "passive+no_connect"))
    )
    (net (code "73") (name "unconnected-(X8-CLKREQ#-Pad7)") (class "Default")
      (node (ref "X8") (pin "7") (pinfunction "CLKREQ#_7") (pintype "passive+no_connect"))
    )
    (net (code "74") (name "unconnected-(X8-LED_WLAN#-Pad44)") (class "Default")
      (node (ref "X8") (pin "44") (pinfunction "LED_WLAN#_44") (pintype "passive+no_connect"))
    )
    (net (code "75") (name "unconnected-(X8-LED_WPAN#-Pad46)") (class "Default")
      (node (ref "X8") (pin "46") (pinfunction "LED_WPAN#_46") (pintype "passive+no_connect"))
    )
    (net (code "76") (name "unconnected-(X8-LED_WWAN#-Pad42)") (class "Default")
      (node (ref "X8") (pin "42") (pinfunction "LED_WWAN#_42") (pintype "passive+no_connect"))
    )
    (net (code "77") (name "unconnected-(X8-PERST#-Pad22)") (class "Default")
      (node (ref "X8") (pin "22") (pinfunction "PERST#_22") (pintype "passive+no_connect"))
    )
    (net (code "78") (name "unconnected-(X8-PERn0-Pad23)") (class "Default")
      (node (ref "X8") (pin "23") (pinfunction "PERn0_23") (pintype "passive+no_connect"))
    )
    (net (code "79") (name "unconnected-(X8-PERp0-Pad25)") (class "Default")
      (node (ref "X8") (pin "25") (pinfunction "PERp0_25") (pintype "passive+no_connect"))
    )
    (net (code "80") (name "unconnected-(X8-PETn0-Pad31)") (class "Default")
      (node (ref "X8") (pin "31") (pinfunction "PETn0_31") (pintype "passive+no_connect"))
    )
    (net (code "81") (name "unconnected-(X8-REFCLK+-Pad13)") (class "Default")
      (node (ref "X8") (pin "13") (pinfunction "REFCLK+_13") (pintype "passive+no_connect"))
    )
    (net (code "82") (name "unconnected-(X8-REFCLK--Pad11)") (class "Default")
      (node (ref "X8") (pin "11") (pinfunction "REFCLK-_11") (pintype "passive+no_connect"))
    )
    (net (code "83") (name "unconnected-(X8-Reserved-Pad17)") (class "Default")
      (node (ref "X8") (pin "17") (pinfunction "Reserved_17") (pintype "passive+no_connect"))
    )
    (net (code "84") (name "unconnected-(X8-Reserved-Pad19)") (class "Default")
      (node (ref "X8") (pin "19") (pinfunction "Reserved_19") (pintype "passive+no_connect"))
    )
    (net (code "85") (name "unconnected-(X8-Reserved-Pad45)") (class "Default")
      (node (ref "X8") (pin "45") (pinfunction "Reserved_45") (pintype "passive+no_connect"))
    )
    (net (code "86") (name "unconnected-(X8-Reserved-Pad47)") (class "Default")
      (node (ref "X8") (pin "47") (pinfunction "Reserved_47") (pintype "passive+no_connect"))
    )
    (net (code "87") (name "unconnected-(X8-Reserved-Pad49)") (class "Default")
      (node (ref "X8") (pin "49") (pinfunction "Reserved_49") (pintype "passive+no_connect"))
    )
    (net (code "88") (name "unconnected-(X8-Reserved-Pad51)") (class "Default")
      (node (ref "X8") (pin "51") (pinfunction "Reserved_51") (pintype "passive+no_connect"))
    )
    (net (code "89") (name "unconnected-(X8-SMB_CLK-Pad30)") (class "Default")
      (node (ref "X8") (pin "30") (pinfunction "SMB_CLK_30") (pintype "passive+no_connect"))
    )
    (net (code "90") (name "unconnected-(X8-SMB_DATA-Pad32)") (class "Default")
      (node (ref "X8") (pin "32") (pinfunction "SMB_DATA_32") (pintype "passive+no_connect"))
    )
    (net (code "91") (name "unconnected-(X8-WAKE#-Pad1)") (class "Default")
      (node (ref "X8") (pin "1") (pinfunction "WAKE#_1") (pintype "passive+no_connect"))
    )
    (net (code "92") (name "unconnected-(X8-W_DISABLE#-Pad20)") (class "Default")
      (node (ref "X8") (pin "20") (pinfunction "W_DISABLE#_20") (pintype "passive+no_connect"))
    )
    (net (code "93") (name "unconnected-(X8-РЕТр0-Pad33)") (class "Default")
      (node (ref "X8") (pin "33") (pinfunction "РЕТр0_33") (pintype "passive+no_connect"))
    )
    (net (code "94") (name "unconnected-(X8-СОЕХ1-Pad3)") (class "Default")
      (node (ref "X8") (pin "3") (pinfunction "СОЕХ1_3") (pintype "passive+no_connect"))
    )
    (net (code "95") (name "unconnected-(X8-СОЕХ2-Pad5)") (class "Default")
      (node (ref "X8") (pin "5") (pinfunction "СОЕХ2_5") (pintype "passive+no_connect"))
    )
    (net (code "96") (name "unconnected-(X11-SH-PadSH1)") (class "Default")
      (node (ref "X11") (pin "SH1") (pinfunction "SH_SH1") (pintype "passive+no_connect"))
    )
    (net (code "97") (name "unconnected-(X11-SH-PadSH2)") (class "Default")
      (node (ref "X11") (pin "SH2") (pinfunction "SH_SH2") (pintype "passive+no_connect"))
    )
    (net (code "98") (name "unconnected-(X11-SH-PadSH3)") (class "Default")
      (node (ref "X11") (pin "SH3") (pinfunction "SH_SH3") (pintype "passive+no_connect"))
    )
    (net (code "99") (name "unconnected-(X11-SH-PadSH5)") (class "Default")
      (node (ref "X11") (pin "SH5") (pinfunction "SH_SH5") (pintype "passive+no_connect"))
    )
    (net (code "100") (name "unconnected-(X11-SH-PadSH6)") (class "Default")
      (node (ref "X11") (pin "SH6") (pinfunction "SH_SH6") (pintype "passive+no_connect"))
    )
    (net (code "101") (name "unconnected-(X11-SH-PadSH7)") (class "Default")
      (node (ref "X11") (pin "SH7") (pinfunction "SH_SH7") (pintype "passive+no_connect"))
    )
    (net (code "102") (name "unconnected-(X12-SH-PadSH2)") (class "Default")
      (node (ref "X12") (pin "SH2") (pinfunction "SH_SH2") (pintype "passive+no_connect"))
    )
    (net (code "103") (name "unconnected-(X12-SH-PadSH3)") (class "Default")
      (node (ref "X12") (pin "SH3") (pinfunction "SH_SH3") (pintype "passive+no_connect"))
    )
    (net (code "104") (name "unconnected-(X12-SH-PadSH4)") (class "Default")
      (node (ref "X12") (pin "SH4") (pinfunction "SH_SH4") (pintype "passive+no_connect"))
    )
    (net (code "105") (name "unconnected-(X12-SH-PadSH5)") (class "Default")
      (node (ref "X12") (pin "SH5") (pinfunction "SH_SH5") (pintype "passive+no_connect"))
    )
    (net (code "106") (name "unconnected-(X12-SH-PadSH6)") (class "Default")
      (node (ref "X12") (pin "SH6") (pinfunction "SH_SH6") (pintype "passive+no_connect"))
    )
    (net (code "107") (name "unconnected-(X12-SH-PadSH7)") (class "Default")
      (node (ref "X12") (pin "SH7") (pinfunction "SH_SH7") (pintype "passive+no_connect"))
    )
  )
)
